# eNode.net
KiCad netlist of a schematic drawn in EAGLE
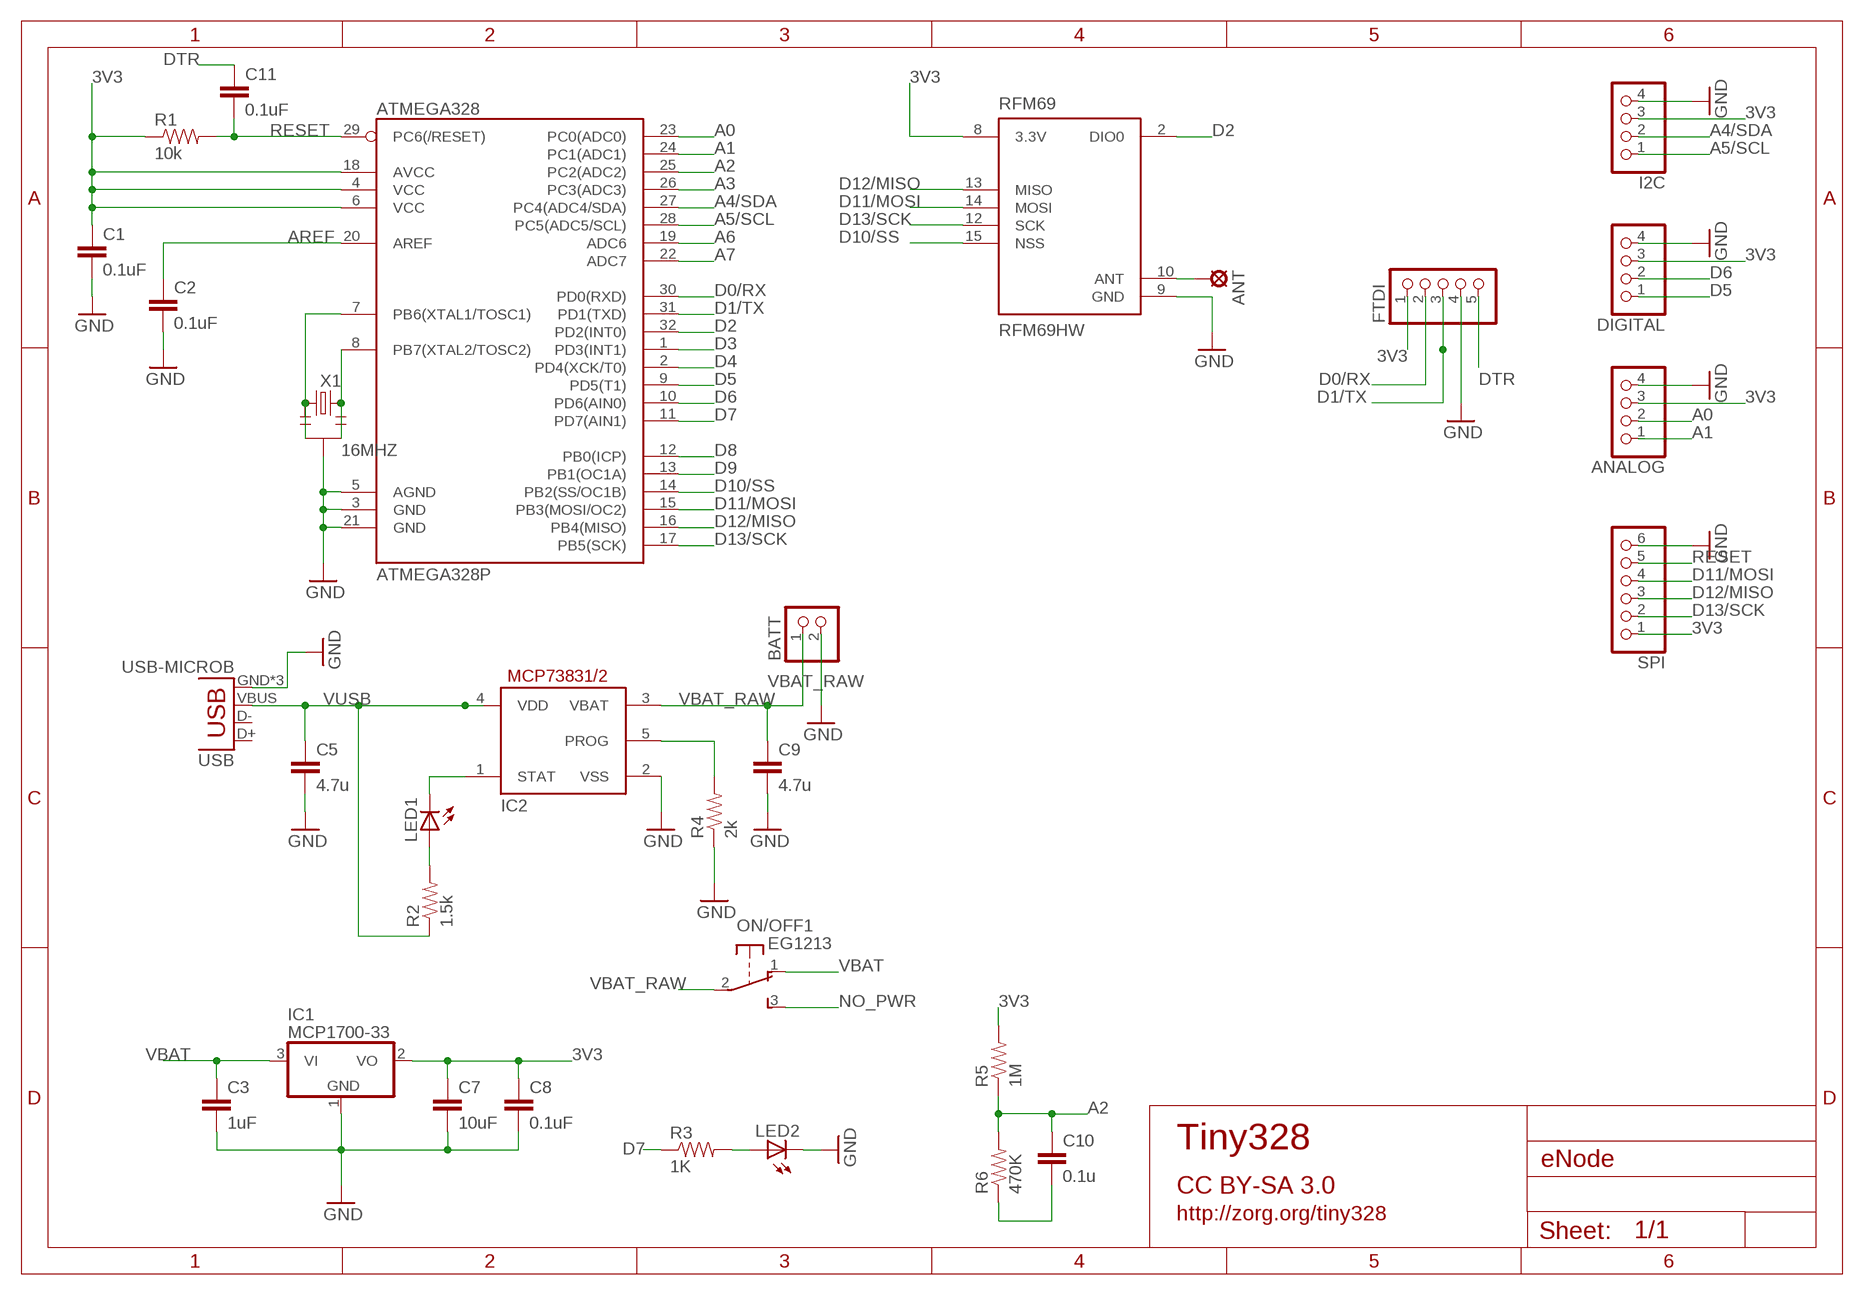
[diagram p0: schematic, sheet 1]

(export (version "E")
  (design (tool "Eeschema 10.0.6"))
  (components
    (comp (ref "ANALOG")
      (value "PINHD-1X4")
      (footprint "eagle-import:1X04")
      (libsource (lib "eagle-import") (part "PINHD-1X4"))
    )
    (comp (ref "ANT")
      (value "LSP10")
      (footprint "eagle-import:LSP10")
      (libsource (lib "eagle-import") (part "LSP10"))
    )
    (comp (ref "ATMEGA328P")
      (value "ATMEGA328")
      (footprint "eagle-import:TQFP32-08")
      (libsource (lib "eagle-import") (part "ATMEGA168"))
    )
    (comp (ref "BATT")
      (value "PINHD-1X2")
      (footprint "eagle-import:1X02")
      (libsource (lib "eagle-import") (part "PINHD-1X2"))
    )
    (comp (ref "C1")
      (value "0.1uF")
      (footprint "eagle-import:0603-CAP")
      (libsource (lib "eagle-import") (part "CAP0603-CAP"))
    )
    (comp (ref "C2")
      (value "0.1uF")
      (footprint "eagle-import:0603-CAP")
      (libsource (lib "eagle-import") (part "CAP0603-CAP"))
    )
    (comp (ref "C3")
      (value "1uF")
      (footprint "eagle-import:0603-CAP")
      (libsource (lib "eagle-import") (part "CAP0603-CAP"))
    )
    (comp (ref "C5")
      (value "4.7u")
      (footprint "eagle-import:0603-CAP")
      (libsource (lib "eagle-import") (part "CAP0603-CAP"))
    )
    (comp (ref "C7")
      (value "10uF")
      (footprint "eagle-import:0603-CAP")
      (libsource (lib "eagle-import") (part "CAP0603-CAP"))
    )
    (comp (ref "C8")
      (value "0.1uF")
      (footprint "eagle-import:0603-CAP")
      (libsource (lib "eagle-import") (part "CAP0603-CAP"))
    )
    (comp (ref "C9")
      (value "4.7u")
      (footprint "eagle-import:0603-CAP")
      (libsource (lib "eagle-import") (part "CAP0603-CAP"))
    )
    (comp (ref "C10")
      (value "0.1u")
      (footprint "eagle-import:0603-CAP")
      (libsource (lib "eagle-import") (part "CAP0603-CAP"))
    )
    (comp (ref "C11")
      (value "0.1uF")
      (footprint "eagle-import:0603-CAP")
      (libsource (lib "eagle-import") (part "CAP0603-CAP"))
    )
    (comp (ref "DIGITAL")
      (value "PINHD-1X4")
      (footprint "eagle-import:1X04")
      (libsource (lib "eagle-import") (part "PINHD-1X4"))
    )
    (comp (ref "FTDI")
      (value "PINHD-1X5")
      (footprint "eagle-import:1X05")
      (libsource (lib "eagle-import") (part "PINHD-1X5"))
    )
    (comp (ref "I2C")
      (value "PINHD-1X4")
      (footprint "eagle-import:1X04")
      (libsource (lib "eagle-import") (part "PINHD-1X4"))
    )
    (comp (ref "IC1")
      (value "MCP1700-33")
      (footprint "eagle-import:SOT23")
      (libsource (lib "eagle-import") (part "MCP1703CB"))
    )
    (comp (ref "IC2")
      (value "MCP73831/OT")
      (footprint "eagle-import:SOT23-5L")
      (libsource (lib "eagle-import") (part "MCP73831/OT"))
    )
    (comp (ref "LED1")
      (value "LEDCHIPLED_0603")
      (footprint "eagle-import:CHIPLED_0603")
      (libsource (lib "eagle-import") (part "LEDCHIPLED_0603"))
    )
    (comp (ref "LED2")
      (value "LEDCHIPLED_0603")
      (footprint "eagle-import:CHIPLED_0603")
      (libsource (lib "eagle-import") (part "LEDCHIPLED_0603"))
    )
    (comp (ref "ON/OFF")
      (value "EG1213")
      (footprint "eagle-import:EG1213")
      (libsource (lib "eagle-import") (part "EG1213"))
    )
    (comp (ref "R1")
      (value "10k")
      (footprint "eagle-import:0603-RES")
      (libsource (lib "eagle-import") (part "RESISTOR0603-RES"))
    )
    (comp (ref "R2")
      (value "1.5k")
      (footprint "eagle-import:0603-RES")
      (libsource (lib "eagle-import") (part "RESISTOR0603-RES"))
    )
    (comp (ref "R3")
      (value "1K")
      (footprint "eagle-import:0603-RES")
      (libsource (lib "eagle-import") (part "RESISTOR0603-RES"))
    )
    (comp (ref "R4")
      (value "2k")
      (footprint "eagle-import:0603-RES")
      (libsource (lib "eagle-import") (part "RESISTOR0603-RES"))
    )
    (comp (ref "R5")
      (value "1M")
      (footprint "eagle-import:0603-RES")
      (libsource (lib "eagle-import") (part "RESISTOR0603-RES"))
    )
    (comp (ref "R6")
      (value "470K")
      (footprint "eagle-import:0603-RES")
      (libsource (lib "eagle-import") (part "RESISTOR0603-RES"))
    )
    (comp (ref "RFM69")
      (value "RFM69HW")
      (footprint "eagle-import:RFM69W-XXXS2")
      (libsource (lib "eagle-import") (part "RFM69HW"))
    )
    (comp (ref "SPI")
      (value "PINHD-1X6")
      (footprint "eagle-import:1X06")
      (libsource (lib "eagle-import") (part "PINHD-1X6"))
    )
    (comp (ref "USB")
      (value "USB-MICROB")
      (footprint "eagle-import:USB-MICROB")
      (libsource (lib "eagle-import") (part "USB-MICROB"))
    )
    (comp (ref "X1")
      (value "16MHZ")
      (footprint "eagle-import:RESONATOR-SMD")
      (libsource (lib "eagle-import") (part "RESONATOR16MHZ"))
    )
  )
  (nets
    (net (code "1") (name "/3V3") (class "Default")
      (node (ref "ANALOG") (pin "3") (pinfunction "3_3") (pintype "passive"))
      (node (ref "ATMEGA328P") (pin "18") (pinfunction "AVCC_18") (pintype "bidirectional"))
      (node (ref "ATMEGA328P") (pin "4") (pinfunction "VCC_4") (pintype "bidirectional"))
      (node (ref "ATMEGA328P") (pin "6") (pinfunction "VCC_6") (pintype "bidirectional"))
      (node (ref "C1") (pin "1") (pinfunction "1_1") (pintype "passive"))
      (node (ref "C7") (pin "1") (pinfunction "1_1") (pintype "passive"))
      (node (ref "C8") (pin "1") (pinfunction "1_1") (pintype "passive"))
      (node (ref "DIGITAL") (pin "3") (pinfunction "3_3") (pintype "passive"))
      (node (ref "FTDI") (pin "1") (pinfunction "1_1") (pintype "passive"))
      (node (ref "I2C") (pin "3") (pinfunction "3_3") (pintype "passive"))
      (node (ref "IC1") (pin "2") (pinfunction "VO_2") (pintype "passive"))
      (node (ref "R1") (pin "1") (pinfunction "1_1") (pintype "passive"))
      (node (ref "R5") (pin "2") (pinfunction "2_2") (pintype "passive"))
      (node (ref "RFM69") (pin "8") (pinfunction "3.3V_8") (pintype "power_in"))
      (node (ref "SPI") (pin "1") (pinfunction "1_1") (pintype "passive"))
    )
    (net (code "2") (name "/A0") (class "Default")
      (node (ref "ANALOG") (pin "2") (pinfunction "2_2") (pintype "passive"))
      (node (ref "ATMEGA328P") (pin "23") (pinfunction "PC0(ADC0)_23") (pintype "bidirectional"))
    )
    (net (code "3") (name "/A1") (class "Default")
      (node (ref "ANALOG") (pin "1") (pinfunction "1_1") (pintype "passive"))
      (node (ref "ATMEGA328P") (pin "24") (pinfunction "PC1(ADC1)_24") (pintype "bidirectional"))
    )
    (net (code "4") (name "/A2") (class "Default")
      (node (ref "ATMEGA328P") (pin "25") (pinfunction "PC2(ADC2)_25") (pintype "bidirectional"))
      (node (ref "C10") (pin "1") (pinfunction "1_1") (pintype "passive"))
      (node (ref "R5") (pin "1") (pinfunction "1_1") (pintype "passive"))
      (node (ref "R6") (pin "2") (pinfunction "2_2") (pintype "passive"))
    )
    (net (code "5") (name "/A3") (class "Default")
      (node (ref "ATMEGA328P") (pin "26") (pinfunction "PC3(ADC3)_26") (pintype "bidirectional"))
    )
    (net (code "6") (name "/A4{slash}SDA") (class "Default")
      (node (ref "ATMEGA328P") (pin "27") (pinfunction "PC4(ADC4/SDA)_27") (pintype "bidirectional"))
      (node (ref "I2C") (pin "2") (pinfunction "2_2") (pintype "passive"))
    )
    (net (code "7") (name "/A5{slash}SCL") (class "Default")
      (node (ref "ATMEGA328P") (pin "28") (pinfunction "PC5(ADC5/SCL)_28") (pintype "bidirectional"))
      (node (ref "I2C") (pin "1") (pinfunction "1_1") (pintype "passive"))
    )
    (net (code "8") (name "/A6") (class "Default")
      (node (ref "ATMEGA328P") (pin "19") (pinfunction "ADC6_19") (pintype "bidirectional"))
    )
    (net (code "9") (name "/A7") (class "Default")
      (node (ref "ATMEGA328P") (pin "22") (pinfunction "ADC7_22") (pintype "bidirectional"))
    )
    (net (code "10") (name "/AREF") (class "Default")
      (node (ref "ATMEGA328P") (pin "20") (pinfunction "AREF_20") (pintype "bidirectional"))
      (node (ref "C2") (pin "1") (pinfunction "1_1") (pintype "passive"))
    )
    (net (code "11") (name "/D0{slash}RX") (class "Default")
      (node (ref "ATMEGA328P") (pin "30") (pinfunction "PD0(RXD)_30") (pintype "bidirectional"))
      (node (ref "FTDI") (pin "2") (pinfunction "2_2") (pintype "passive"))
    )
    (net (code "12") (name "/D1{slash}TX") (class "Default")
      (node (ref "ATMEGA328P") (pin "31") (pinfunction "PD1(TXD)_31") (pintype "bidirectional"))
      (node (ref "FTDI") (pin "3") (pinfunction "3_3") (pintype "passive"))
    )
    (net (code "13") (name "/D2") (class "Default")
      (node (ref "ATMEGA328P") (pin "32") (pinfunction "PD2(INT0)_32") (pintype "bidirectional"))
      (node (ref "RFM69") (pin "2") (pinfunction "DIO0_2") (pintype "bidirectional"))
    )
    (net (code "14") (name "/D3") (class "Default")
      (node (ref "ATMEGA328P") (pin "1") (pinfunction "PD3(INT1)_1") (pintype "bidirectional"))
    )
    (net (code "15") (name "/D4") (class "Default")
      (node (ref "ATMEGA328P") (pin "2") (pinfunction "PD4(XCK/T0)_2") (pintype "bidirectional"))
    )
    (net (code "16") (name "/D5") (class "Default")
      (node (ref "ATMEGA328P") (pin "9") (pinfunction "PD5(T1)_9") (pintype "bidirectional"))
      (node (ref "DIGITAL") (pin "1") (pinfunction "1_1") (pintype "passive"))
    )
    (net (code "17") (name "/D6") (class "Default")
      (node (ref "ATMEGA328P") (pin "10") (pinfunction "PD6(AIN0)_10") (pintype "bidirectional"))
      (node (ref "DIGITAL") (pin "2") (pinfunction "2_2") (pintype "passive"))
    )
    (net (code "18") (name "/D7") (class "Default")
      (node (ref "ATMEGA328P") (pin "11") (pinfunction "PD7(AIN1)_11") (pintype "bidirectional"))
      (node (ref "R3") (pin "1") (pinfunction "1_1") (pintype "passive"))
    )
    (net (code "19") (name "/D8") (class "Default")
      (node (ref "ATMEGA328P") (pin "12") (pinfunction "PB0(ICP)_12") (pintype "bidirectional"))
    )
    (net (code "20") (name "/D9") (class "Default")
      (node (ref "ATMEGA328P") (pin "13") (pinfunction "PB1(OC1A)_13") (pintype "bidirectional"))
    )
    (net (code "21") (name "/D10{slash}SS") (class "Default")
      (node (ref "ATMEGA328P") (pin "14") (pinfunction "PB2(SS/OC1B)_14") (pintype "bidirectional"))
      (node (ref "RFM69") (pin "15") (pinfunction "NSS_15") (pintype "input"))
    )
    (net (code "22") (name "/D11{slash}MOSI") (class "Default")
      (node (ref "ATMEGA328P") (pin "15") (pinfunction "PB3(MOSI/OC2)_15") (pintype "bidirectional"))
      (node (ref "RFM69") (pin "14") (pinfunction "MOSI_14") (pintype "input"))
      (node (ref "SPI") (pin "4") (pinfunction "4_4") (pintype "passive"))
    )
    (net (code "23") (name "/D12{slash}MISO") (class "Default")
      (node (ref "ATMEGA328P") (pin "16") (pinfunction "PB4(MISO)_16") (pintype "bidirectional"))
      (node (ref "RFM69") (pin "13") (pinfunction "MISO_13") (pintype "bidirectional"))
      (node (ref "SPI") (pin "3") (pinfunction "3_3") (pintype "passive"))
    )
    (net (code "24") (name "/D13{slash}SCK") (class "Default")
      (node (ref "ATMEGA328P") (pin "17") (pinfunction "PB5(SCK)_17") (pintype "bidirectional"))
      (node (ref "RFM69") (pin "12") (pinfunction "SCK_12") (pintype "input"))
      (node (ref "SPI") (pin "2") (pinfunction "2_2") (pintype "passive"))
    )
    (net (code "25") (name "/DTR") (class "Default")
      (node (ref "C11") (pin "1") (pinfunction "1_1") (pintype "passive"))
      (node (ref "FTDI") (pin "5") (pinfunction "5_5") (pintype "passive"))
    )
    (net (code "26") (name "/NO_PWR") (class "Default")
      (node (ref "ON/OFF") (pin "3") (pinfunction "S_3") (pintype "passive"))
    )
    (net (code "27") (name "/RESET") (class "Default")
      (node (ref "ATMEGA328P") (pin "29") (pinfunction "PC6(/RESET)_29") (pintype "bidirectional"))
      (node (ref "C11") (pin "2") (pinfunction "2_2") (pintype "passive"))
      (node (ref "R1") (pin "2") (pinfunction "2_2") (pintype "passive"))
      (node (ref "SPI") (pin "5") (pinfunction "5_5") (pintype "passive"))
    )
    (net (code "28") (name "/VBAT") (class "Default")
      (node (ref "C3") (pin "1") (pinfunction "1_1") (pintype "passive"))
      (node (ref "IC1") (pin "3") (pinfunction "VI_3") (pintype "input"))
      (node (ref "ON/OFF") (pin "1") (pinfunction "O_1") (pintype "passive"))
    )
    (net (code "29") (name "/VBAT_RAW") (class "Default")
      (node (ref "BATT") (pin "1") (pinfunction "1_1") (pintype "passive"))
      (node (ref "C9") (pin "1") (pinfunction "1_1") (pintype "passive"))
      (node (ref "IC2") (pin "3") (pinfunction "VBAT_3") (pintype "bidirectional"))
      (node (ref "ON/OFF") (pin "2") (pinfunction "P_2") (pintype "passive"))
    )
    (net (code "30") (name "/VUSB") (class "Default")
      (node (ref "C5") (pin "1") (pinfunction "1_1") (pintype "passive"))
      (node (ref "IC2") (pin "4") (pinfunction "VDD_4") (pintype "power_in"))
      (node (ref "R2") (pin "1") (pinfunction "1_1") (pintype "passive"))
      (node (ref "USB") (pin "VBUS") (pinfunction "VBUS_VBUS") (pintype "bidirectional"))
    )
    (net (code "31") (name "GND") (class "Default")
      (node (ref "ANALOG") (pin "4") (pinfunction "4_4") (pintype "passive"))
      (node (ref "ATMEGA328P") (pin "21") (pinfunction "GND_21") (pintype "bidirectional"))
      (node (ref "ATMEGA328P") (pin "3") (pinfunction "GND_3") (pintype "bidirectional"))
      (node (ref "ATMEGA328P") (pin "5") (pinfunction "AGND_5") (pintype "bidirectional"))
      (node (ref "BATT") (pin "2") (pinfunction "2_2") (pintype "passive"))
      (node (ref "C1") (pin "2") (pinfunction "2_2") (pintype "passive"))
      (node (ref "C2") (pin "2") (pinfunction "2_2") (pintype "passive"))
      (node (ref "C3") (pin "2") (pinfunction "2_2") (pintype "passive"))
      (node (ref "C5") (pin "2") (pinfunction "2_2") (pintype "passive"))
      (node (ref "C7") (pin "2") (pinfunction "2_2") (pintype "passive"))
      (node (ref "C8") (pin "2") (pinfunction "2_2") (pintype "passive"))
      (node (ref "C9") (pin "2") (pinfunction "2_2") (pintype "passive"))
      (node (ref "DIGITAL") (pin "4") (pinfunction "4_4") (pintype "passive"))
      (node (ref "FTDI") (pin "4") (pinfunction "4_4") (pintype "passive"))
      (node (ref "I2C") (pin "4") (pinfunction "4_4") (pintype "passive"))
      (node (ref "IC1") (pin "1") (pinfunction "GND_1") (pintype "passive"))
      (node (ref "IC2") (pin "2") (pinfunction "VSS_2") (pintype "power_in"))
      (node (ref "LED2") (pin "C") (pinfunction "C_C") (pintype "passive"))
      (node (ref "R4") (pin "1") (pinfunction "1_1") (pintype "passive"))
      (node (ref "RFM69") (pin "9") (pinfunction "GND_9") (pintype "power_in"))
      (node (ref "SPI") (pin "6") (pinfunction "6_6") (pintype "passive"))
      (node (ref "USB") (pin "GND") (pinfunction "GND_GND") (pintype "bidirectional"))
      (node (ref "USB") (pin "MT1") (pinfunction "GND_MT1") (pintype "bidirectional"))
      (node (ref "USB") (pin "MT2") (pinfunction "GND_MT2") (pintype "bidirectional"))
      (node (ref "X1") (pin "2") (pinfunction "2_2") (pintype "passive"))
    )
    (net (code "32") (name "Net-(ATMEGA328P-PB6(XTAL1{slash}TOSC1))") (class "Default")
      (node (ref "ATMEGA328P") (pin "7") (pinfunction "PB6(XTAL1/TOSC1)_7") (pintype "bidirectional"))
      (node (ref "X1") (pin "1") (pinfunction "1_1") (pintype "passive"))
    )
    (net (code "33") (name "Net-(ATMEGA328P-PB7(XTAL2{slash}TOSC2))") (class "Default")
      (node (ref "ATMEGA328P") (pin "8") (pinfunction "PB7(XTAL2/TOSC2)_8") (pintype "bidirectional"))
      (node (ref "X1") (pin "3") (pinfunction "3_3") (pintype "passive"))
    )
    (net (code "34") (name "Net-(C10-Pad2)") (class "Default")
      (node (ref "C10") (pin "2") (pinfunction "2_2") (pintype "passive"))
      (node (ref "R6") (pin "1") (pinfunction "1_1") (pintype "passive"))
    )
    (net (code "35") (name "Net-(IC2-PROG)") (class "Default")
      (node (ref "IC2") (pin "5") (pinfunction "PROG_5") (pintype "input"))
      (node (ref "R4") (pin "2") (pinfunction "2_2") (pintype "passive"))
    )
    (net (code "36") (name "Net-(IC2-STAT)") (class "Default")
      (node (ref "IC2") (pin "1") (pinfunction "STAT_1") (pintype "output"))
      (node (ref "LED1") (pin "C") (pinfunction "C_C") (pintype "passive"))
    )
    (net (code "37") (name "Net-(LED1-PadA)") (class "Default")
      (node (ref "LED1") (pin "A") (pinfunction "A_A") (pintype "passive"))
      (node (ref "R2") (pin "2") (pinfunction "2_2") (pintype "passive"))
    )
    (net (code "38") (name "Net-(LED2-PadA)") (class "Default")
      (node (ref "LED2") (pin "A") (pinfunction "A_A") (pintype "passive"))
      (node (ref "R3") (pin "2") (pinfunction "2_2") (pintype "passive"))
    )
    (net (code "39") (name "Net-(RFM69-ANT)") (class "Default")
      (node (ref "ANT") (pin "MP") (pinfunction "MP_MP") (pintype "passive"))
      (node (ref "RFM69") (pin "10") (pinfunction "ANT_10") (pintype "passive"))
    )
    (net (code "40") (name "unconnected-(USB-PadD+)") (class "Default")
      (node (ref "USB") (pin "D+") (pinfunction "D+_D+") (pintype "bidirectional"))
    )
    (net (code "41") (name "unconnected-(USB-PadD-)") (class "Default")
      (node (ref "USB") (pin "D-") (pinfunction "D-_D-") (pintype "bidirectional"))
    )
  )
)
